# power-ac_rev_1.net
KiCad netlist of a schematic drawn in EAGLE
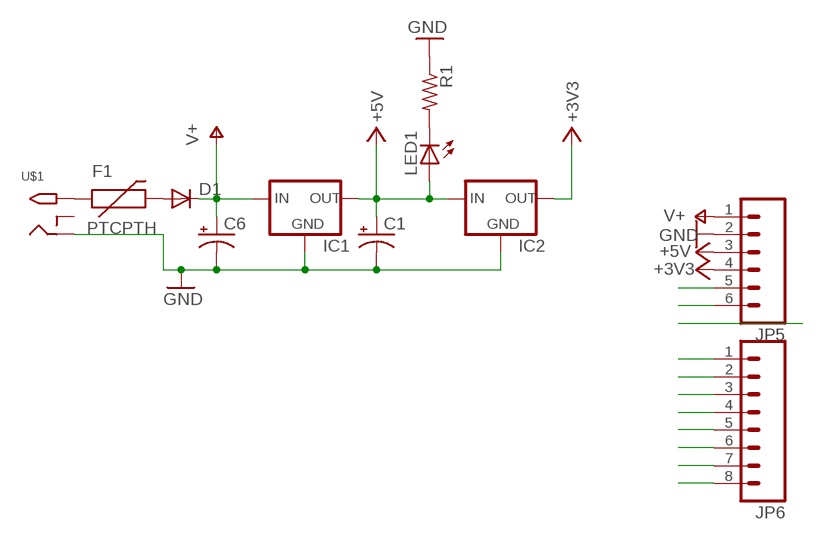
[diagram p0: schematic, sheet 1]

(export (version "E")
  (design (tool "Eeschema 10.0.6"))
  (components
    (comp (ref "C1")
      (value "CAP_POLPTH1")
      (footprint "eagle-import:CPOL-RADIAL-100UF-25V")
      (libsource (lib "eagle-import") (part "CAP_POLPTH1"))
    )
    (comp (ref "C6")
      (value "CAP_POLPTH1")
      (footprint "eagle-import:CPOL-RADIAL-100UF-25V")
      (libsource (lib "eagle-import") (part "CAP_POLPTH1"))
    )
    (comp (ref "D1")
      (value "DIODE1N4148")
      (footprint "eagle-import:DIODE-1N4148")
      (libsource (lib "eagle-import") (part "DIODE1N4148"))
    )
    (comp (ref "F1")
      (value "PTCPTH")
      (footprint "eagle-import:PTC")
      (libsource (lib "eagle-import") (part "PTCPTH"))
    )
    (comp (ref "IC1")
      (value "V_REG_78XX-TO-220")
      (footprint "eagle-import:TO-220-ALT")
      (libsource (lib "eagle-import") (part "V_REG_78XX-TO-220"))
    )
    (comp (ref "IC2")
      (value "MCP1700INLINE")
      (footprint "eagle-import:TO92-INLINE")
      (libsource (lib "eagle-import") (part "MCP1700INLINE"))
    )
    (comp (ref "JP5")
      (value "M06SIP")
      (footprint "eagle-import:1X06")
      (libsource (lib "eagle-import") (part "M06SIP"))
    )
    (comp (ref "JP6")
      (value "M081X08")
      (footprint "eagle-import:1X08")
      (libsource (lib "eagle-import") (part "M081X08"))
    )
    (comp (ref "LED1")
      (value "LED3MM")
      (footprint "eagle-import:LED3MM")
      (libsource (lib "eagle-import") (part "LED3MM"))
    )
    (comp (ref "R1")
      (value "R-US_0204/2V")
      (footprint "eagle-import:0204V")
      (libsource (lib "eagle-import") (part "R-US_0204/2V"))
    )
    (comp (ref "U$1")
      (value "2.1MMJACKTHM")
      (footprint "eagle-import:PJ-102A")
      (libsource (lib "eagle-import") (part "2.1MMJACKTHM"))
    )
  )
  (nets
    (net (code "1") (name "+3V3") (class "Default")
      (node (ref "IC2") (pin "3") (pinfunction "OUT_3") (pintype "passive"))
      (node (ref "JP5") (pin "4") (pinfunction "4_4") (pintype "passive"))
    )
    (net (code "2") (name "+5V") (class "Default")
      (node (ref "C1") (pin "1") (pinfunction "+_1") (pintype "passive"))
      (node (ref "IC1") (pin "OUT") (pinfunction "OUT_OUT") (pintype "output"))
      (node (ref "IC2") (pin "2") (pinfunction "IN_2") (pintype "input"))
      (node (ref "JP5") (pin "3") (pinfunction "3_3") (pintype "passive"))
      (node (ref "LED1") (pin "A") (pinfunction "A_A") (pintype "passive"))
    )
    (net (code "3") (name "GND") (class "Default")
      (node (ref "C1") (pin "2") (pinfunction "-_2") (pintype "passive"))
      (node (ref "C6") (pin "2") (pinfunction "-_2") (pintype "passive"))
      (node (ref "IC1") (pin "GND") (pinfunction "GND_GND") (pintype "input"))
      (node (ref "IC2") (pin "1") (pinfunction "GND_1") (pintype "input"))
      (node (ref "JP5") (pin "2") (pinfunction "2_2") (pintype "passive"))
      (node (ref "R1") (pin "1") (pinfunction "1_1") (pintype "passive"))
      (node (ref "U$1") (pin "RING") (pinfunction "RING_RING") (pintype "bidirectional"))
    )
    (net (code "4") (name "Net-(F1-1)") (class "Default")
      (node (ref "F1") (pin "P$1") (pinfunction "1_P$1") (pintype "bidirectional"))
      (node (ref "U$1") (pin "TIP") (pinfunction "TIP_TIP") (pintype "bidirectional"))
    )
    (net (code "5") (name "Net-(F1-2)") (class "Default")
      (node (ref "D1") (pin "A") (pinfunction "A_A") (pintype "passive"))
      (node (ref "F1") (pin "P$2") (pinfunction "2_P$2") (pintype "bidirectional"))
    )
    (net (code "6") (name "Net-(LED1-C)") (class "Default")
      (node (ref "LED1") (pin "K") (pinfunction "C_K") (pintype "passive"))
      (node (ref "R1") (pin "2") (pinfunction "2_2") (pintype "passive"))
    )
    (net (code "7") (name "V+") (class "Default")
      (node (ref "C6") (pin "1") (pinfunction "+_1") (pintype "passive"))
      (node (ref "D1") (pin "C") (pinfunction "C_C") (pintype "passive"))
      (node (ref "IC1") (pin "IN") (pinfunction "IN_IN") (pintype "input"))
      (node (ref "JP5") (pin "1") (pinfunction "1_1") (pintype "passive"))
    )
    (net (code "8") (name "unconnected-(JP5-Pad5)") (class "Default")
      (node (ref "JP5") (pin "5") (pinfunction "5_5") (pintype "passive"))
    )
    (net (code "9") (name "unconnected-(JP5-Pad6)") (class "Default")
      (node (ref "JP5") (pin "6") (pinfunction "6_6") (pintype "passive"))
    )
    (net (code "10") (name "unconnected-(JP6-Pad1)") (class "Default")
      (node (ref "JP6") (pin "1") (pinfunction "1_1") (pintype "passive"))
    )
    (net (code "11") (name "unconnected-(JP6-Pad2)") (class "Default")
      (node (ref "JP6") (pin "2") (pinfunction "2_2") (pintype "passive"))
    )
    (net (code "12") (name "unconnected-(JP6-Pad3)") (class "Default")
      (node (ref "JP6") (pin "3") (pinfunction "3_3") (pintype "passive"))
    )
    (net (code "13") (name "unconnected-(JP6-Pad4)") (class "Default")
      (node (ref "JP6") (pin "4") (pinfunction "4_4") (pintype "passive"))
    )
    (net (code "14") (name "unconnected-(JP6-Pad5)") (class "Default")
      (node (ref "JP6") (pin "5") (pinfunction "5_5") (pintype "passive"))
    )
    (net (code "15") (name "unconnected-(JP6-Pad6)") (class "Default")
      (node (ref "JP6") (pin "6") (pinfunction "6_6") (pintype "passive"))
    )
    (net (code "16") (name "unconnected-(JP6-Pad7)") (class "Default")
      (node (ref "JP6") (pin "7") (pinfunction "7_7") (pintype "passive"))
    )
    (net (code "17") (name "unconnected-(JP6-Pad8)") (class "Default")
      (node (ref "JP6") (pin "8") (pinfunction "8_8") (pintype "passive"))
    )
    (net (code "18") (name "unconnected-(U$1-PadRING_SW)") (class "Default")
      (node (ref "U$1") (pin "RING_SW") (pinfunction "RING_SW_RING_SW") (pintype "bidirectional"))
    )
  )
)
